# Sheet1.net
KiCad netlist of a schematic drawn in Altium Designer
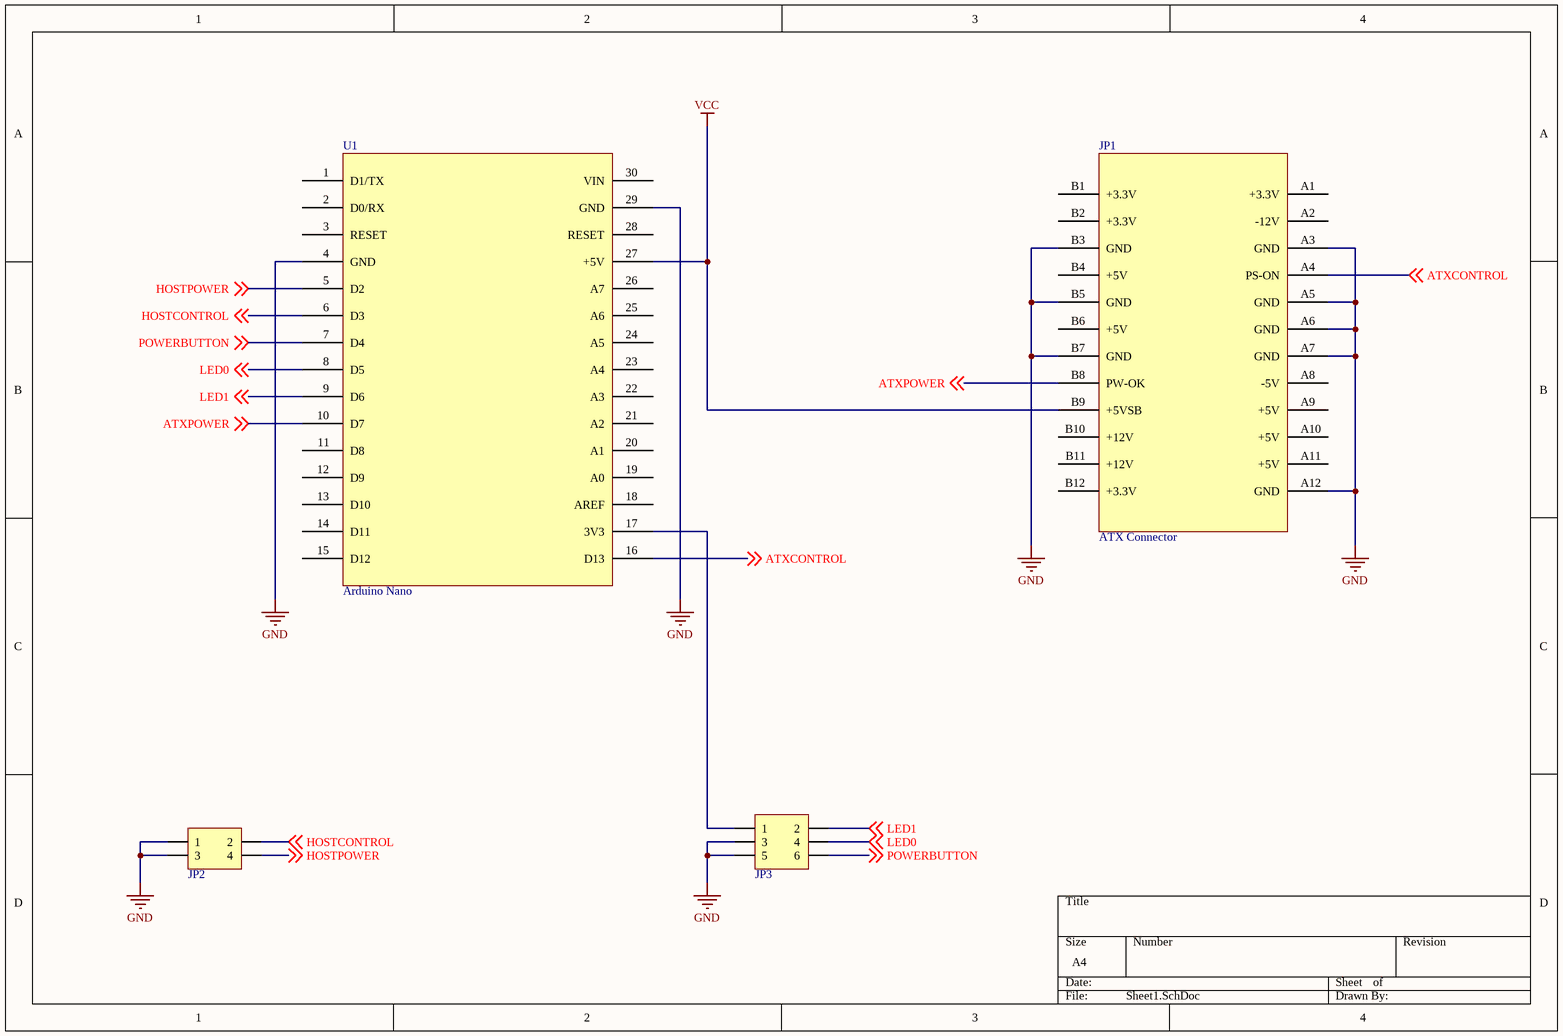
[diagram p0: Sheet1.SchDoc]

(export (version "E")
  (design (tool "Eeschema 10.0.6"))
  (components
    (comp (ref "JP1")
      (value "ATX Connector")
      (footprint "ATX Connector")
      (description "4.2mm间距 5557-20P/24P 焊板式 板对板 连接器 2*12直针座")
      (libsource (lib "HSchlib") (part "ATX Connector"))
    )
    (comp (ref "JP2")
      (value "Header2X2")
      (footprint "HDR2.54-LI-2x2P")
      (description "2*2P接插件")
      (fields (field (name "版权归属") "封装库来自淘宝 ID：黄晶宝石"))
      (libsource (lib "5.4 - 接插件-脚距2.54 (100mil) ") (part "Header 2X2"))
    )
    (comp (ref "JP3")
      (value "Header3X2")
      (footprint "HDR2.54-LI-2x3P")
      (description "3*2P接插件")
      (fields (field (name "版权归属") "封装库来自淘宝 ID：黄晶宝石"))
      (libsource (lib "5.4 - 接插件-脚距2.54 (100mil) ") (part "Header 3X2"))
    )
    (comp (ref "U1")
      (value "Arduino Nano")
      (footprint "ArduinoNanoDIP30")
      (description "Arduino Nano Board V3.0")
      (libsource (lib "HSchlib") (part "Arduino Nano"))
    )
  )
  (nets
    (net (code "1") (name "ATXCONTROL") (class "Default")
      (node (ref "JP1") (pin "A4") (pinfunction "PS-ON_A4") (pintype "passive"))
      (node (ref "U1") (pin "16") (pinfunction "D13_16") (pintype "passive"))
    )
    (net (code "2") (name "ATXPOWER") (class "Default")
      (node (ref "JP1") (pin "B8") (pinfunction "PW-OK_B8") (pintype "passive"))
      (node (ref "U1") (pin "10") (pinfunction "D7_10") (pintype "passive"))
    )
    (net (code "3") (name "GND") (class "Default")
      (node (ref "JP1") (pin "A12") (pinfunction "GND_A12") (pintype "passive"))
      (node (ref "JP1") (pin "A3") (pinfunction "GND_A3") (pintype "passive"))
      (node (ref "JP1") (pin "A5") (pinfunction "GND_A5") (pintype "passive"))
      (node (ref "JP1") (pin "A6") (pinfunction "GND_A6") (pintype "passive"))
      (node (ref "JP1") (pin "A7") (pinfunction "GND_A7") (pintype "passive"))
      (node (ref "JP1") (pin "B3") (pinfunction "GND_B3") (pintype "passive"))
      (node (ref "JP1") (pin "B5") (pinfunction "GND_B5") (pintype "passive"))
      (node (ref "JP1") (pin "B7") (pinfunction "GND_B7") (pintype "passive"))
      (node (ref "JP2") (pin "1") (pinfunction "1_1") (pintype "passive"))
      (node (ref "JP2") (pin "3") (pinfunction "3_3") (pintype "passive"))
      (node (ref "JP3") (pin "3") (pinfunction "3_3") (pintype "passive"))
      (node (ref "JP3") (pin "5") (pinfunction "5_5") (pintype "passive"))
      (node (ref "U1") (pin "29") (pinfunction "GND_29") (pintype "passive"))
      (node (ref "U1") (pin "4") (pinfunction "GND_4") (pintype "passive"))
    )
    (net (code "4") (name "HOSTCONTROL") (class "Default")
      (node (ref "JP2") (pin "2") (pinfunction "2_2") (pintype "passive"))
      (node (ref "U1") (pin "6") (pinfunction "D3_6") (pintype "passive"))
    )
    (net (code "5") (name "HOSTPOWER") (class "Default")
      (node (ref "JP2") (pin "4") (pinfunction "4_4") (pintype "passive"))
      (node (ref "U1") (pin "5") (pinfunction "D2_5") (pintype "passive"))
    )
    (net (code "6") (name "LED0") (class "Default")
      (node (ref "JP3") (pin "4") (pinfunction "4_4") (pintype "passive"))
      (node (ref "U1") (pin "8") (pinfunction "D5_8") (pintype "passive"))
    )
    (net (code "7") (name "LED1") (class "Default")
      (node (ref "JP3") (pin "2") (pinfunction "2_2") (pintype "passive"))
      (node (ref "U1") (pin "9") (pinfunction "D6_9") (pintype "passive"))
    )
    (net (code "8") (name "Net-(U1-3V3)") (class "Default")
      (node (ref "JP3") (pin "1") (pinfunction "1_1") (pintype "passive"))
      (node (ref "U1") (pin "17") (pinfunction "3V3_17") (pintype "passive"))
    )
    (net (code "9") (name "POWERBUTTON") (class "Default")
      (node (ref "JP3") (pin "6") (pinfunction "6_6") (pintype "passive"))
      (node (ref "U1") (pin "7") (pinfunction "D4_7") (pintype "passive"))
    )
    (net (code "10") (name "VCC") (class "Default")
      (node (ref "JP1") (pin "B9") (pinfunction "+5VSB_B9") (pintype "passive"))
      (node (ref "U1") (pin "27") (pinfunction "+5V_27") (pintype "passive"))
    )
    (net (code "11") (name "unconnected-(JP1-+3.3V-PadA1)") (class "Default")
      (node (ref "JP1") (pin "A1") (pinfunction "+3.3V_A1") (pintype "passive"))
    )
    (net (code "12") (name "unconnected-(JP1-+3.3V-PadB1)") (class "Default")
      (node (ref "JP1") (pin "B1") (pinfunction "+3.3V_B1") (pintype "passive"))
    )
    (net (code "13") (name "unconnected-(JP1-+3.3V-PadB2)") (class "Default")
      (node (ref "JP1") (pin "B2") (pinfunction "+3.3V_B2") (pintype "passive"))
    )
    (net (code "14") (name "unconnected-(JP1-+3.3V-PadB12)") (class "Default")
      (node (ref "JP1") (pin "B12") (pinfunction "+3.3V_B12") (pintype "passive"))
    )
    (net (code "15") (name "unconnected-(JP1-+5V-PadA9)") (class "Default")
      (node (ref "JP1") (pin "A9") (pinfunction "+5V_A9") (pintype "passive"))
    )
    (net (code "16") (name "unconnected-(JP1-+5V-PadA10)") (class "Default")
      (node (ref "JP1") (pin "A10") (pinfunction "+5V_A10") (pintype "passive"))
    )
    (net (code "17") (name "unconnected-(JP1-+5V-PadA11)") (class "Default")
      (node (ref "JP1") (pin "A11") (pinfunction "+5V_A11") (pintype "passive"))
    )
    (net (code "18") (name "unconnected-(JP1-+5V-PadB4)") (class "Default")
      (node (ref "JP1") (pin "B4") (pinfunction "+5V_B4") (pintype "passive"))
    )
    (net (code "19") (name "unconnected-(JP1-+5V-PadB6)") (class "Default")
      (node (ref "JP1") (pin "B6") (pinfunction "+5V_B6") (pintype "passive"))
    )
    (net (code "20") (name "unconnected-(JP1-+12V-PadB10)") (class "Default")
      (node (ref "JP1") (pin "B10") (pinfunction "+12V_B10") (pintype "passive"))
    )
    (net (code "21") (name "unconnected-(JP1-+12V-PadB11)") (class "Default")
      (node (ref "JP1") (pin "B11") (pinfunction "+12V_B11") (pintype "passive"))
    )
    (net (code "22") (name "unconnected-(JP1--5V-PadA8)") (class "Default")
      (node (ref "JP1") (pin "A8") (pinfunction "-5V_A8") (pintype "passive"))
    )
    (net (code "23") (name "unconnected-(JP1--12V-PadA2)") (class "Default")
      (node (ref "JP1") (pin "A2") (pinfunction "-12V_A2") (pintype "passive"))
    )
    (net (code "24") (name "unconnected-(U1-A0-Pad19)") (class "Default")
      (node (ref "U1") (pin "19") (pinfunction "A0_19") (pintype "passive"))
    )
    (net (code "25") (name "unconnected-(U1-A1-Pad20)") (class "Default")
      (node (ref "U1") (pin "20") (pinfunction "A1_20") (pintype "passive"))
    )
    (net (code "26") (name "unconnected-(U1-A2-Pad21)") (class "Default")
      (node (ref "U1") (pin "21") (pinfunction "A2_21") (pintype "passive"))
    )
    (net (code "27") (name "unconnected-(U1-A3-Pad22)") (class "Default")
      (node (ref "U1") (pin "22") (pinfunction "A3_22") (pintype "passive"))
    )
    (net (code "28") (name "unconnected-(U1-A4-Pad23)") (class "Default")
      (node (ref "U1") (pin "23") (pinfunction "A4_23") (pintype "passive"))
    )
    (net (code "29") (name "unconnected-(U1-A5-Pad24)") (class "Default")
      (node (ref "U1") (pin "24") (pinfunction "A5_24") (pintype "passive"))
    )
    (net (code "30") (name "unconnected-(U1-A6-Pad25)") (class "Default")
      (node (ref "U1") (pin "25") (pinfunction "A6_25") (pintype "passive"))
    )
    (net (code "31") (name "unconnected-(U1-A7-Pad26)") (class "Default")
      (node (ref "U1") (pin "26") (pinfunction "A7_26") (pintype "passive"))
    )
    (net (code "32") (name "unconnected-(U1-AREF-Pad18)") (class "Default")
      (node (ref "U1") (pin "18") (pinfunction "AREF_18") (pintype "passive"))
    )
    (net (code "33") (name "unconnected-(U1-D0{slash}RX-Pad2)") (class "Default")
      (node (ref "U1") (pin "2") (pinfunction "D0/RX_2") (pintype "passive"))
    )
    (net (code "34") (name "unconnected-(U1-D1{slash}TX-Pad1)") (class "Default")
      (node (ref "U1") (pin "1") (pinfunction "D1/TX_1") (pintype "passive"))
    )
    (net (code "35") (name "unconnected-(U1-D8-Pad11)") (class "Default")
      (node (ref "U1") (pin "11") (pinfunction "D8_11") (pintype "passive"))
    )
    (net (code "36") (name "unconnected-(U1-D9-Pad12)") (class "Default")
      (node (ref "U1") (pin "12") (pinfunction "D9_12") (pintype "passive"))
    )
    (net (code "37") (name "unconnected-(U1-D10-Pad13)") (class "Default")
      (node (ref "U1") (pin "13") (pinfunction "D10_13") (pintype "passive"))
    )
    (net (code "38") (name "unconnected-(U1-D11-Pad14)") (class "Default")
      (node (ref "U1") (pin "14") (pinfunction "D11_14") (pintype "passive"))
    )
    (net (code "39") (name "unconnected-(U1-D12-Pad15)") (class "Default")
      (node (ref "U1") (pin "15") (pinfunction "D12_15") (pintype "passive"))
    )
    (net (code "40") (name "unconnected-(U1-RESET-Pad3)") (class "Default")
      (node (ref "U1") (pin "3") (pinfunction "RESET_3") (pintype "passive"))
    )
    (net (code "41") (name "unconnected-(U1-RESET-Pad28)") (class "Default")
      (node (ref "U1") (pin "28") (pinfunction "RESET_28") (pintype "passive"))
    )
    (net (code "42") (name "unconnected-(U1-VIN-Pad30)") (class "Default")
      (node (ref "U1") (pin "30") (pinfunction "VIN_30") (pintype "passive"))
    )
  )
)
